# UsbBatteryAnalyzer.net
KiCad netlist of a schematic drawn in EAGLE
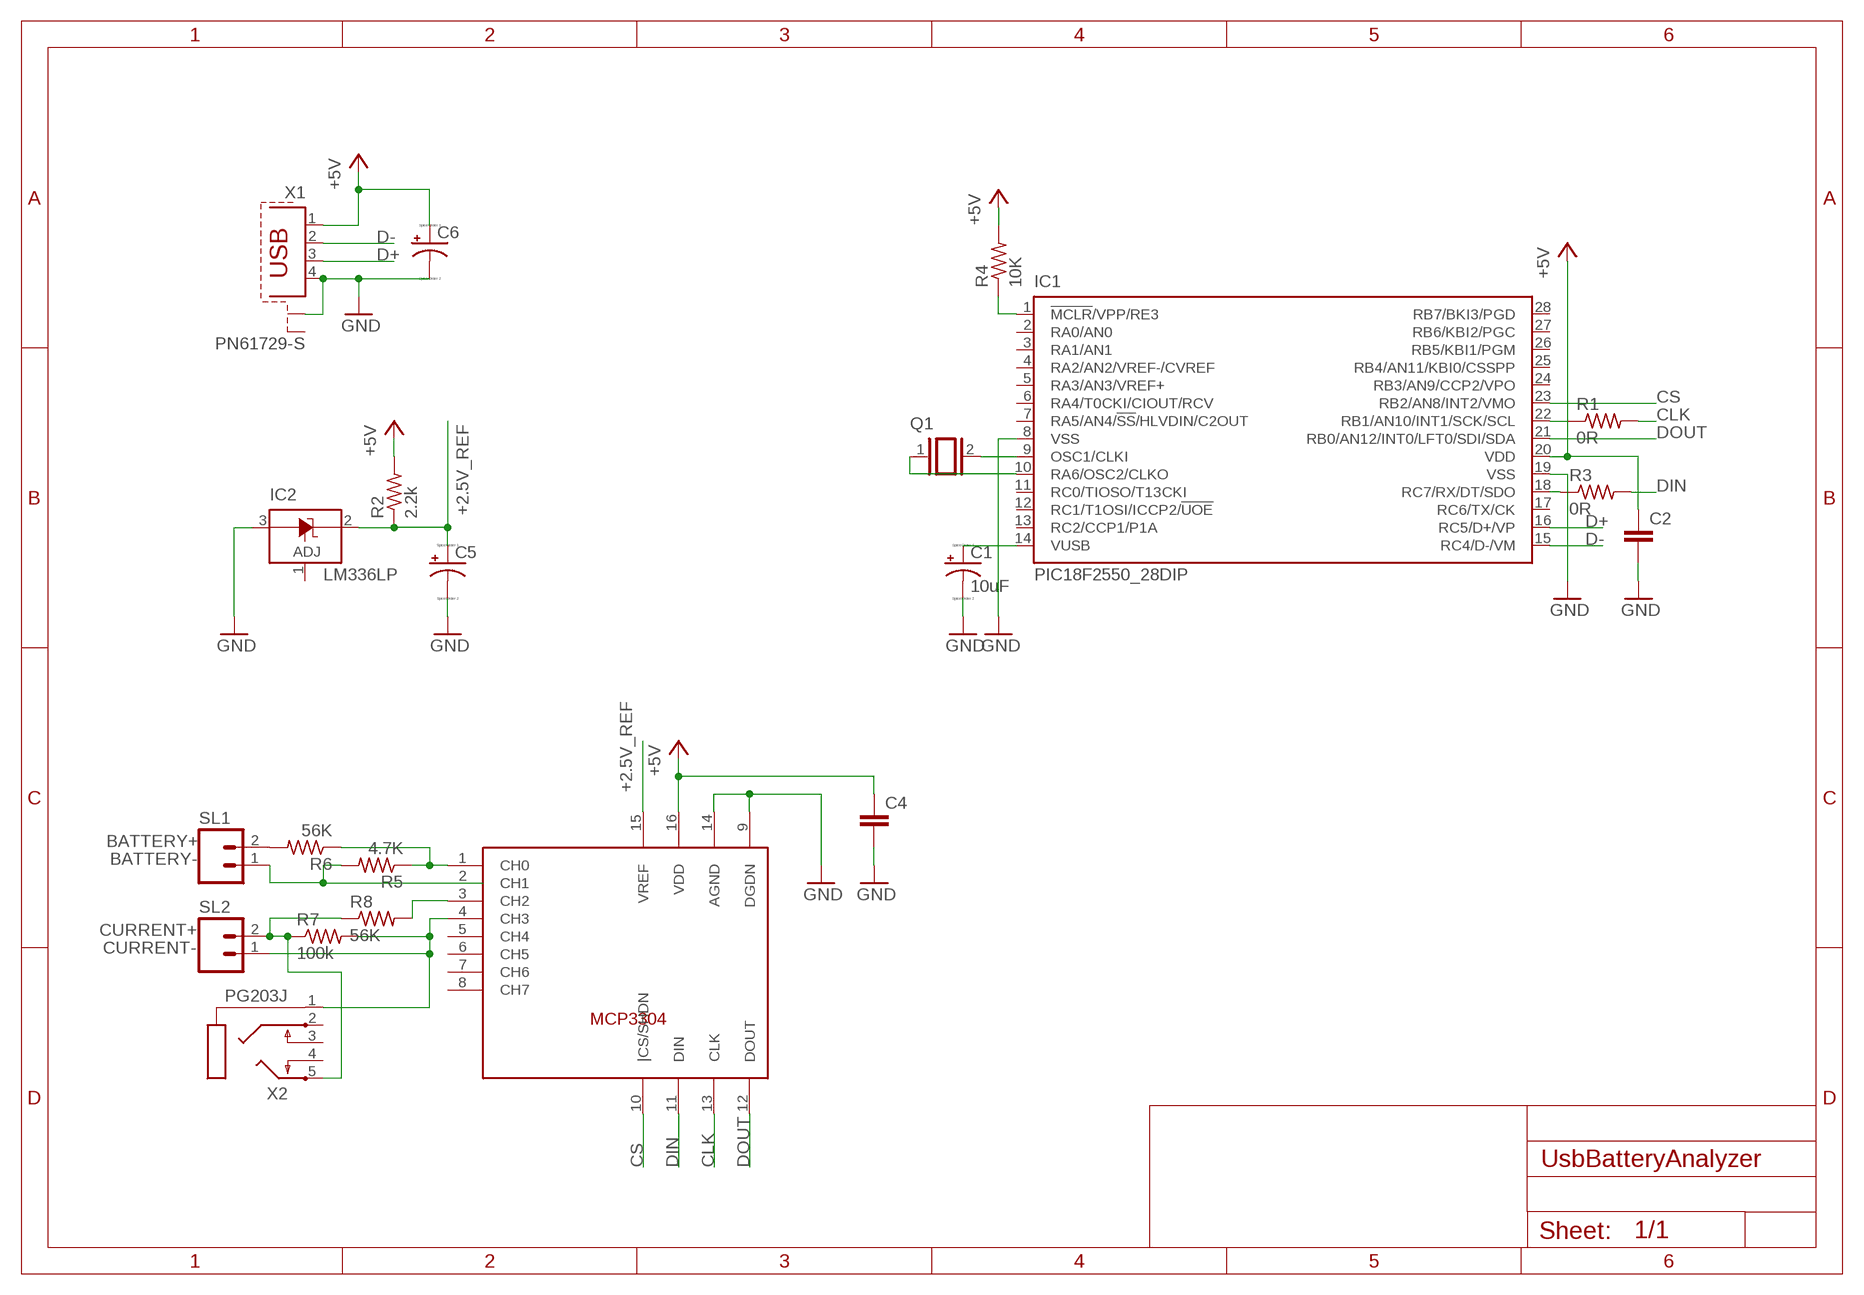
[diagram p0: schematic, sheet 1]

(export (version "E")
  (design (tool "Eeschema 10.0.6"))
  (components
    (comp (ref "C1")
      (value "10uF")
      (footprint "eagle-import:E2,5-7")
      (libsource (lib "eagle-import") (part "CPOL-USE2.5-7"))
    )
    (comp (ref "C2")
      (value "C-EU050-024X044")
      (footprint "eagle-import:C050-024X044")
      (libsource (lib "eagle-import") (part "C-EU050-024X044"))
    )
    (comp (ref "C4")
      (value "C-EU050-024X044")
      (footprint "eagle-import:C050-024X044")
      (libsource (lib "eagle-import") (part "C-EU050-024X044"))
    )
    (comp (ref "C5")
      (value "CPOL-USE2.5-7")
      (footprint "eagle-import:E2,5-7")
      (libsource (lib "eagle-import") (part "CPOL-USE2.5-7"))
    )
    (comp (ref "C6")
      (value "CPOL-USE2.5-7")
      (footprint "eagle-import:E2,5-7")
      (libsource (lib "eagle-import") (part "CPOL-USE2.5-7"))
    )
    (comp (ref "IC1")
      (value "PIC18F2550_28DIP")
      (footprint "eagle-import:DIL28-3")
      (fields (field (name "MF") "MICROCHIP") (field (name "MPN") "PIC18F2550-I/SP"))
      (libsource (lib "eagle-import") (part "PIC18F2_28DIP550"))
    )
    (comp (ref "IC2")
      (value "LM336LP")
      (footprint "eagle-import:TO92")
      (libsource (lib "eagle-import") (part "LM336LP"))
    )
    (comp (ref "Q1")
      (value "XTAL/S")
      (footprint "eagle-import:QS")
      (libsource (lib "eagle-import") (part "XTAL/S"))
    )
    (comp (ref "R1")
      (value "0R")
      (footprint "eagle-import:0207_5V")
      (libsource (lib "eagle-import") (part "R-US_0207/5V"))
    )
    (comp (ref "R2")
      (value "2.2k")
      (footprint "eagle-import:0204_7")
      (libsource (lib "eagle-import") (part "R-US_0204/7"))
    )
    (comp (ref "R3")
      (value "0R")
      (footprint "eagle-import:0207_10")
      (libsource (lib "eagle-import") (part "R-US_0207/10"))
    )
    (comp (ref "R4")
      (value "10K")
      (footprint "eagle-import:0204_7")
      (libsource (lib "eagle-import") (part "R-US_0204/7"))
    )
    (comp (ref "R5")
      (value "4.7K")
      (footprint "eagle-import:0204_7")
      (libsource (lib "eagle-import") (part "R-US_0204/7"))
    )
    (comp (ref "R6")
      (value "56K")
      (footprint "eagle-import:0204_7")
      (libsource (lib "eagle-import") (part "resistor_R-US_0204/7"))
    )
    (comp (ref "R7")
      (value "100k")
      (footprint "eagle-import:0204_7")
      (libsource (lib "eagle-import") (part "R-US_0204/7"))
    )
    (comp (ref "R8")
      (value "56K")
      (footprint "eagle-import:0204_7")
      (libsource (lib "eagle-import") (part "R-US_0204/7"))
    )
    (comp (ref "SL1")
      (value "M02")
      (footprint "eagle-import:02P")
      (libsource (lib "eagle-import") (part "M02"))
    )
    (comp (ref "SL2")
      (value "M02")
      (footprint "eagle-import:02P")
      (libsource (lib "eagle-import") (part "M02"))
    )
    (comp (ref "U$1")
      (value "MCP3304")
      (footprint "eagle-import:DIP16")
      (libsource (lib "eagle-import") (part "MCP3304"))
    )
    (comp (ref "X1")
      (value "PN61729-S")
      (footprint "eagle-import:PN61729-S")
      (libsource (lib "eagle-import") (part "PN61729-S"))
    )
    (comp (ref "X2")
      (value "PG203J")
      (footprint "eagle-import:PG203J")
      (libsource (lib "eagle-import") (part "PG203J"))
    )
  )
  (nets
    (net (code "1") (name "+5V") (class "Default")
      (node (ref "C2") (pin "1") (pinfunction "1_1") (pintype "passive"))
      (node (ref "C4") (pin "1") (pinfunction "1_1") (pintype "passive"))
      (node (ref "C6") (pin "+") (pinfunction "+_+") (pintype "passive"))
      (node (ref "IC1") (pin "20") (pinfunction "VDD_20") (pintype "power_in"))
      (node (ref "R2") (pin "2") (pinfunction "2_2") (pintype "passive"))
      (node (ref "R4") (pin "2") (pinfunction "2_2") (pintype "passive"))
      (node (ref "U$1") (pin "16") (pinfunction "VDD_16") (pintype "bidirectional"))
      (node (ref "X1") (pin "1") (pinfunction "1_1") (pintype "passive"))
    )
    (net (code "2") (name "/+2.5V_REF") (class "Default")
      (node (ref "C5") (pin "+") (pinfunction "+_+") (pintype "passive"))
      (node (ref "IC2") (pin "2") (pinfunction "C_2") (pintype "passive"))
      (node (ref "R2") (pin "1") (pinfunction "1_1") (pintype "passive"))
      (node (ref "U$1") (pin "15") (pinfunction "VREF_15") (pintype "bidirectional"))
    )
    (net (code "4") (name "/BATTERY+") (class "Default")
      (node (ref "R6") (pin "2") (pinfunction "2_2") (pintype "passive"))
      (node (ref "SL1") (pin "2") (pinfunction "2_2") (pintype "passive"))
    )
    (net (code "5") (name "/BATTERY-") (class "Default")
      (node (ref "R5") (pin "2") (pinfunction "2_2") (pintype "passive"))
      (node (ref "SL1") (pin "1") (pinfunction "1_1") (pintype "passive"))
      (node (ref "U$1") (pin "2") (pinfunction "CH1_2") (pintype "bidirectional"))
    )
    (net (code "6") (name "/CLK") (class "Default")
      (node (ref "R1") (pin "2") (pinfunction "2_2") (pintype "passive"))
      (node (ref "U$1") (pin "13") (pinfunction "CLK_13") (pintype "bidirectional"))
    )
    (net (code "7") (name "/CS") (class "Default")
      (node (ref "IC1") (pin "23") (pinfunction "RB2/AN8/INT2/VMO_23") (pintype "bidirectional"))
      (node (ref "U$1") (pin "10") (pinfunction "|CS/SHDN_10") (pintype "bidirectional"))
    )
    (net (code "8") (name "/CURRENT+") (class "Default")
      (node (ref "R7") (pin "1") (pinfunction "1_1") (pintype "passive"))
      (node (ref "R8") (pin "1") (pinfunction "1_1") (pintype "passive"))
      (node (ref "SL2") (pin "2") (pinfunction "2_2") (pintype "passive"))
      (node (ref "X2") (pin "5") (pinfunction "5_5") (pintype "passive"))
    )
    (net (code "9") (name "/CURRENT-") (class "Default")
      (node (ref "R7") (pin "2") (pinfunction "2_2") (pintype "passive"))
      (node (ref "SL2") (pin "1") (pinfunction "1_1") (pintype "passive"))
      (node (ref "U$1") (pin "4") (pinfunction "CH3_4") (pintype "bidirectional"))
      (node (ref "X2") (pin "1") (pinfunction "1_1") (pintype "passive"))
    )
    (net (code "10") (name "/D+") (class "Default")
      (node (ref "IC1") (pin "16") (pinfunction "RC5/D+/VP_16") (pintype "bidirectional"))
      (node (ref "X1") (pin "3") (pinfunction "3_3") (pintype "passive"))
    )
    (net (code "11") (name "/D-") (class "Default")
      (node (ref "IC1") (pin "15") (pinfunction "RC4/D-/VM_15") (pintype "bidirectional"))
      (node (ref "X1") (pin "2") (pinfunction "2_2") (pintype "passive"))
    )
    (net (code "12") (name "/DIN") (class "Default")
      (node (ref "R3") (pin "2") (pinfunction "2_2") (pintype "passive"))
      (node (ref "U$1") (pin "11") (pinfunction "DIN_11") (pintype "bidirectional"))
    )
    (net (code "13") (name "/DOUT") (class "Default")
      (node (ref "IC1") (pin "21") (pinfunction "RB0/AN12/INT0/LFT0/SDI/SDA_21") (pintype "bidirectional"))
      (node (ref "U$1") (pin "12") (pinfunction "DOUT_12") (pintype "bidirectional"))
    )
    (net (code "14") (name "GND") (class "Default")
      (node (ref "C1") (pin "-") (pinfunction "-_-") (pintype "passive"))
      (node (ref "C2") (pin "2") (pinfunction "2_2") (pintype "passive"))
      (node (ref "C4") (pin "2") (pinfunction "2_2") (pintype "passive"))
      (node (ref "C5") (pin "-") (pinfunction "-_-") (pintype "passive"))
      (node (ref "C6") (pin "-") (pinfunction "-_-") (pintype "passive"))
      (node (ref "IC1") (pin "19") (pinfunction "VSS_19") (pintype "power_in"))
      (node (ref "IC1") (pin "8") (pinfunction "VSS_8") (pintype "power_in"))
      (node (ref "IC2") (pin "3") (pinfunction "A_3") (pintype "input"))
      (node (ref "U$1") (pin "14") (pinfunction "AGND_14") (pintype "bidirectional"))
      (node (ref "U$1") (pin "9") (pinfunction "DGDN_9") (pintype "bidirectional"))
      (node (ref "X1") (pin "4") (pinfunction "4_4") (pintype "passive"))
      (node (ref "X1") (pin "S1") (pinfunction "S1_S1") (pintype "passive"))
    )
    (net (code "15") (name "Net-(IC1-OSC1{slash}CLKI)") (class "Default")
      (node (ref "IC1") (pin "9") (pinfunction "OSC1/CLKI_9") (pintype "input"))
      (node (ref "Q1") (pin "2") (pinfunction "2_2") (pintype "passive"))
    )
    (net (code "16") (name "Net-(IC1-RA6{slash}OSC2{slash}CLKO)") (class "Default")
      (node (ref "IC1") (pin "10") (pinfunction "RA6/OSC2/CLKO_10") (pintype "output"))
      (node (ref "Q1") (pin "1") (pinfunction "1_1") (pintype "passive"))
    )
    (net (code "17") (name "Net-(IC1-RB1{slash}AN10{slash}INT1{slash}SCK{slash}SCL)") (class "Default")
      (node (ref "IC1") (pin "22") (pinfunction "RB1/AN10/INT1/SCK/SCL_22") (pintype "bidirectional"))
      (node (ref "R1") (pin "1") (pinfunction "1_1") (pintype "passive"))
    )
    (net (code "18") (name "Net-(IC1-RC7{slash}RX{slash}DT{slash}SDO)") (class "Default")
      (node (ref "IC1") (pin "18") (pinfunction "RC7/RX/DT/SDO_18") (pintype "bidirectional"))
      (node (ref "R3") (pin "1") (pinfunction "1_1") (pintype "passive"))
    )
    (net (code "19") (name "Net-(IC1-VUSB)") (class "Default")
      (node (ref "C1") (pin "+") (pinfunction "+_+") (pintype "passive"))
      (node (ref "IC1") (pin "14") (pinfunction "VUSB_14") (pintype "bidirectional"))
    )
    (net (code "20") (name "Net-(IC1-~{MCLR}{slash}VPP{slash}RE3)") (class "Default")
      (node (ref "IC1") (pin "1") (pinfunction "~{MCLR}/VPP/RE3_1") (pintype "input"))
      (node (ref "R4") (pin "1") (pinfunction "1_1") (pintype "passive"))
    )
    (net (code "21") (name "Net-(U$1-CH0)") (class "Default")
      (node (ref "R5") (pin "1") (pinfunction "1_1") (pintype "passive"))
      (node (ref "R6") (pin "1") (pinfunction "1_1") (pintype "passive"))
      (node (ref "U$1") (pin "1") (pinfunction "CH0_1") (pintype "bidirectional"))
    )
    (net (code "22") (name "Net-(U$1-CH2)") (class "Default")
      (node (ref "R8") (pin "2") (pinfunction "2_2") (pintype "passive"))
      (node (ref "U$1") (pin "3") (pinfunction "CH2_3") (pintype "bidirectional"))
    )
    (net (code "23") (name "unconnected-(IC1-RA0{slash}AN0-Pad2)") (class "Default")
      (node (ref "IC1") (pin "2") (pinfunction "RA0/AN0_2") (pintype "bidirectional"))
    )
    (net (code "24") (name "unconnected-(IC1-RA1{slash}AN1-Pad3)") (class "Default")
      (node (ref "IC1") (pin "3") (pinfunction "RA1/AN1_3") (pintype "bidirectional"))
    )
    (net (code "25") (name "unconnected-(IC1-RA2{slash}AN2{slash}VREF-{slash}CVREF-Pad4)") (class "Default")
      (node (ref "IC1") (pin "4") (pinfunction "RA2/AN2/VREF-/CVREF_4") (pintype "bidirectional"))
    )
    (net (code "26") (name "unconnected-(IC1-RA3{slash}AN3{slash}VREF+-Pad5)") (class "Default")
      (node (ref "IC1") (pin "5") (pinfunction "RA3/AN3/VREF+_5") (pintype "bidirectional"))
    )
    (net (code "27") (name "unconnected-(IC1-RA4{slash}T0CKI{slash}CIOUT{slash}RCV-Pad6)") (class "Default")
      (node (ref "IC1") (pin "6") (pinfunction "RA4/T0CKI/CIOUT/RCV_6") (pintype "bidirectional"))
    )
    (net (code "28") (name "unconnected-(IC1-RA5{slash}AN4{slash}~{SS}{slash}HLVDIN{slash}C2OUT-Pad7)") (class "Default")
      (node (ref "IC1") (pin "7") (pinfunction "RA5/AN4/~{SS}/HLVDIN/C2OUT_7") (pintype "bidirectional"))
    )
    (net (code "29") (name "unconnected-(IC1-RB3{slash}AN9{slash}CCP2{slash}VPO-Pad24)") (class "Default")
      (node (ref "IC1") (pin "24") (pinfunction "RB3/AN9/CCP2/VPO_24") (pintype "bidirectional"))
    )
    (net (code "30") (name "unconnected-(IC1-RB4{slash}AN11{slash}KBI0{slash}CSSPP-Pad25)") (class "Default")
      (node (ref "IC1") (pin "25") (pinfunction "RB4/AN11/KBI0/CSSPP_25") (pintype "bidirectional"))
    )
    (net (code "31") (name "unconnected-(IC1-RB5{slash}KBI1{slash}PGM-Pad26)") (class "Default")
      (node (ref "IC1") (pin "26") (pinfunction "RB5/KBI1/PGM_26") (pintype "bidirectional"))
    )
    (net (code "32") (name "unconnected-(IC1-RB6{slash}KBI2{slash}PGC-Pad27)") (class "Default")
      (node (ref "IC1") (pin "27") (pinfunction "RB6/KBI2/PGC_27") (pintype "bidirectional"))
    )
    (net (code "33") (name "unconnected-(IC1-RB7{slash}BKI3{slash}PGD-Pad28)") (class "Default")
      (node (ref "IC1") (pin "28") (pinfunction "RB7/BKI3/PGD_28") (pintype "bidirectional"))
    )
    (net (code "34") (name "unconnected-(IC1-RC0{slash}TIOSO{slash}T13CKI-Pad11)") (class "Default")
      (node (ref "IC1") (pin "11") (pinfunction "RC0/TIOSO/T13CKI_11") (pintype "bidirectional"))
    )
    (net (code "35") (name "unconnected-(IC1-RC1{slash}T1OSI{slash}ICCP2{slash}~{UOE}-Pad12)") (class "Default")
      (node (ref "IC1") (pin "12") (pinfunction "RC1/T1OSI/ICCP2/~{UOE}_12") (pintype "bidirectional"))
    )
    (net (code "36") (name "unconnected-(IC1-RC2{slash}CCP1{slash}P1A-Pad13)") (class "Default")
      (node (ref "IC1") (pin "13") (pinfunction "RC2/CCP1/P1A_13") (pintype "bidirectional"))
    )
    (net (code "37") (name "unconnected-(IC1-RC6{slash}TX{slash}CK-Pad17)") (class "Default")
      (node (ref "IC1") (pin "17") (pinfunction "RC6/TX/CK_17") (pintype "bidirectional"))
    )
    (net (code "38") (name "unconnected-(IC2-ADJ-Pad1)") (class "Default")
      (node (ref "IC2") (pin "1") (pinfunction "ADJ_1") (pintype "input"))
    )
    (net (code "39") (name "unconnected-(U$1-CH4-Pad5)") (class "Default")
      (node (ref "U$1") (pin "5") (pinfunction "CH4_5") (pintype "bidirectional"))
    )
    (net (code "40") (name "unconnected-(U$1-CH5-Pad6)") (class "Default")
      (node (ref "U$1") (pin "6") (pinfunction "CH5_6") (pintype "bidirectional"))
    )
    (net (code "41") (name "unconnected-(U$1-CH6-Pad7)") (class "Default")
      (node (ref "U$1") (pin "7") (pinfunction "CH6_7") (pintype "bidirectional"))
    )
    (net (code "42") (name "unconnected-(U$1-CH7-Pad8)") (class "Default")
      (node (ref "U$1") (pin "8") (pinfunction "CH7_8") (pintype "bidirectional"))
    )
    (net (code "43") (name "unconnected-(X1-PadS2)") (class "Default")
      (node (ref "X1") (pin "S2") (pinfunction "S2_S2") (pintype "passive"))
    )
    (net (code "44") (name "unconnected-(X2-Pad2)") (class "Default")
      (node (ref "X2") (pin "2") (pinfunction "2_2") (pintype "passive"))
    )
    (net (code "45") (name "unconnected-(X2-Pad3)") (class "Default")
      (node (ref "X2") (pin "3") (pinfunction "3_3") (pintype "passive"))
    )
    (net (code "46") (name "unconnected-(X2-Pad4)") (class "Default")
      (node (ref "X2") (pin "4") (pinfunction "4_4") (pintype "passive"))
    )
  )
)
